# centerbody_Combine.net
KiCad netlist of a schematic drawn in EAGLE
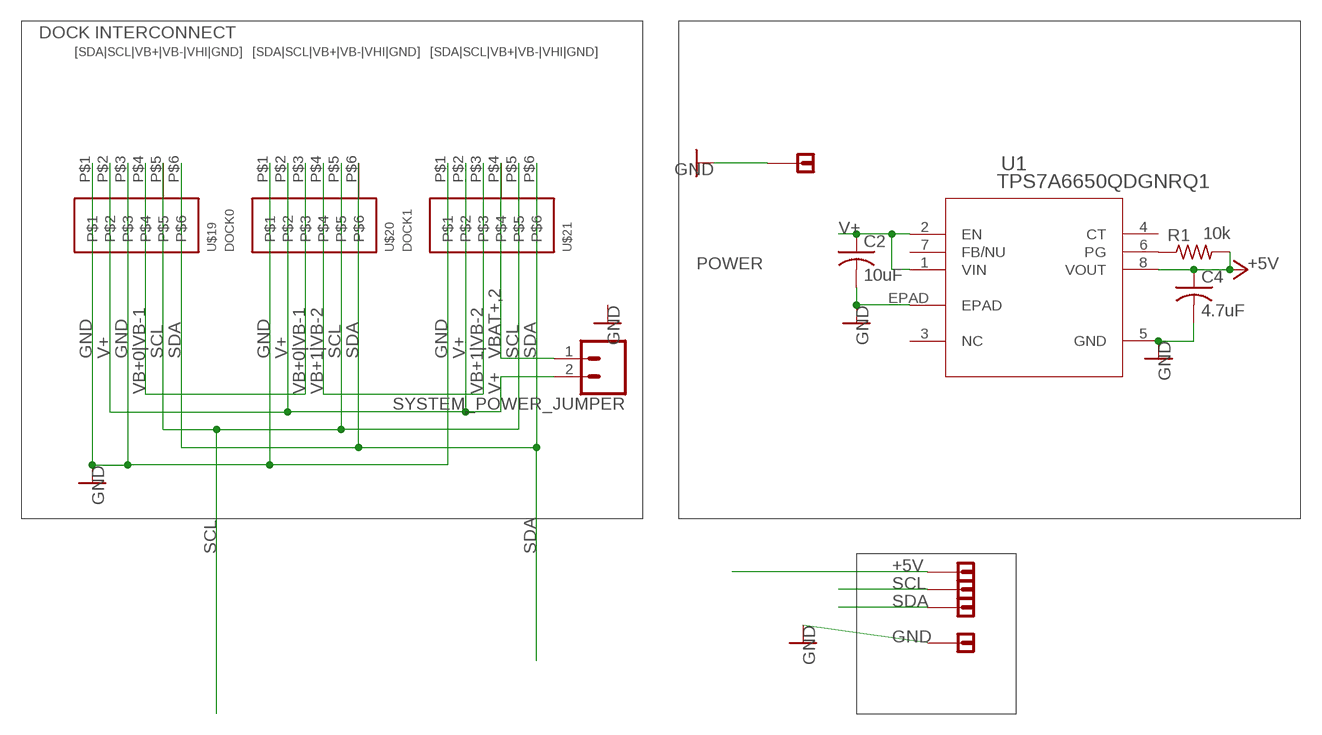
[diagram p0: schematic, sheet 1]

(export (version "E")
  (design (tool "Eeschema 10.0.6"))
  (components
    (comp (ref "C2")
      (value "10uF")
      (footprint "eagle-import:C1206")
      (libsource (lib "eagle-import") (part "C-USC1206"))
    )
    (comp (ref "C4")
      (value "4.7uF")
      (footprint "eagle-import:C0402")
      (libsource (lib "eagle-import") (part "resistor_348_C-USC0402"))
    )
    (comp (ref "R1")
      (value "10k")
      (footprint "eagle-import:R0402")
      (libsource (lib "eagle-import") (part "R-US_R0402"))
    )
    (comp (ref "SYSTEM_POWER_JUMPER")
      (value "CONN_02")
      (footprint "eagle-import:1X02")
      (libsource (lib "eagle-import") (part "CONN_02"))
    )
    (comp (ref "U$1")
      (value "SIMPLE_VIA_CONNECTION")
      (footprint "eagle-import:SIMPLEVIA")
      (libsource (lib "eagle-import") (part "SIMPLE_VIA_CONNECTION"))
    )
    (comp (ref "U$3")
      (value "SIMPLE_VIA_CONNECTION")
      (footprint "eagle-import:SIMPLEVIA")
      (libsource (lib "eagle-import") (part "SIMPLE_VIA_CONNECTION"))
    )
    (comp (ref "U$4")
      (value "SIMPLE_VIA_CONNECTION")
      (footprint "eagle-import:SIMPLEVIA")
      (libsource (lib "eagle-import") (part "SIMPLE_VIA_CONNECTION"))
    )
    (comp (ref "U$7")
      (value "SIMPLE_VIA_CONNECTION")
      (footprint "eagle-import:SIMPLEVIA")
      (libsource (lib "eagle-import") (part "SIMPLE_VIA_CONNECTION"))
    )
    (comp (ref "U$9")
      (value "SIMPLE_VIA_CONNECTION")
      (footprint "eagle-import:SIMPLEVIA")
      (libsource (lib "eagle-import") (part "SIMPLE_VIA_CONNECTION"))
    )
    (comp (ref "U$19")
      (value "DOCK0")
      (footprint "eagle-import:COMPACT_6CONN_STRAIGHT")
      (libsource (lib "eagle-import") (part "COMPACT_6CONNSTRAIGHT"))
    )
    (comp (ref "U$20")
      (value "DOCK1")
      (footprint "eagle-import:COMPACT_6CONN_STRAIGHT")
      (libsource (lib "eagle-import") (part "COMPACT_6CONNSTRAIGHT"))
    )
    (comp (ref "U$21")
      (value "DOCK_2")
      (footprint "eagle-import:COMPACT_6CONN_STRAIGHT")
      (libsource (lib "eagle-import") (part "COMPACT_6CONNSTRAIGHT"))
    )
    (comp (ref "U1")
      (value "TPS7A6650QDGNRQ1")
      (footprint "eagle-import:DGN8_1P57X1P89")
      (libsource (lib "eagle-import") (part "TPS7A6650QDGNRQ1"))
    )
  )
  (nets
    (net (code "1") (name "+5V") (class "Default")
      (node (ref "C4") (pin "1") (pinfunction "1_1") (pintype "passive"))
      (node (ref "R1") (pin "2") (pinfunction "2_2") (pintype "passive"))
      (node (ref "U$7") (pin "P$1") (pinfunction "1_P$1") (pintype "passive"))
      (node (ref "U1") (pin "8") (pinfunction "VOUT_8") (pintype "output"))
    )
    (net (code "2") (name "/SCL") (class "Default")
      (node (ref "U$19") (pin "P$5") (pinfunction "P$5_P$5") (pintype "bidirectional"))
      (node (ref "U$20") (pin "P$5") (pinfunction "P$5_P$5") (pintype "bidirectional"))
      (node (ref "U$21") (pin "P$5") (pinfunction "P$5_P$5") (pintype "bidirectional"))
      (node (ref "U$9") (pin "P$1") (pinfunction "1_P$1") (pintype "passive"))
    )
    (net (code "3") (name "/SDA") (class "Default")
      (node (ref "U$19") (pin "P$6") (pinfunction "P$6_P$6") (pintype "bidirectional"))
      (node (ref "U$20") (pin "P$6") (pinfunction "P$6_P$6") (pintype "bidirectional"))
      (node (ref "U$21") (pin "P$6") (pinfunction "P$6_P$6") (pintype "bidirectional"))
      (node (ref "U$4") (pin "P$1") (pinfunction "1_P$1") (pintype "passive"))
    )
    (net (code "4") (name "/V+") (class "Default")
      (node (ref "C2") (pin "1") (pinfunction "1_1") (pintype "passive"))
      (node (ref "SYSTEM_POWER_JUMPER") (pin "2") (pinfunction "2_2") (pintype "passive"))
      (node (ref "U$19") (pin "P$2") (pinfunction "P$2_P$2") (pintype "bidirectional"))
      (node (ref "U$20") (pin "P$2") (pinfunction "P$2_P$2") (pintype "bidirectional"))
      (node (ref "U$21") (pin "P$2") (pinfunction "P$2_P$2") (pintype "bidirectional"))
      (node (ref "U1") (pin "1") (pinfunction "VIN_1") (pintype "input"))
      (node (ref "U1") (pin "2") (pinfunction "EN_2") (pintype "input"))
    )
    (net (code "5") (name "/VB+0|VB-1") (class "Default")
      (node (ref "U$19") (pin "P$4") (pinfunction "P$4_P$4") (pintype "bidirectional"))
      (node (ref "U$20") (pin "P$3") (pinfunction "P$3_P$3") (pintype "bidirectional"))
    )
    (net (code "6") (name "/VB+1|VB-2") (class "Default")
      (node (ref "U$20") (pin "P$4") (pinfunction "P$4_P$4") (pintype "bidirectional"))
      (node (ref "U$21") (pin "P$3") (pinfunction "P$3_P$3") (pintype "bidirectional"))
    )
    (net (code "7") (name "/VBAT+,2") (class "Default")
      (node (ref "SYSTEM_POWER_JUMPER") (pin "1") (pinfunction "1_1") (pintype "passive"))
      (node (ref "U$21") (pin "P$4") (pinfunction "P$4_P$4") (pintype "bidirectional"))
    )
    (net (code "8") (name "GND") (class "Default")
      (node (ref "C2") (pin "2") (pinfunction "2_2") (pintype "passive"))
      (node (ref "C4") (pin "2") (pinfunction "2_2") (pintype "passive"))
      (node (ref "U$1") (pin "P$1") (pinfunction "1_P$1") (pintype "passive"))
      (node (ref "U$19") (pin "P$1") (pinfunction "P$1_P$1") (pintype "bidirectional"))
      (node (ref "U$19") (pin "P$3") (pinfunction "P$3_P$3") (pintype "bidirectional"))
      (node (ref "U$20") (pin "P$1") (pinfunction "P$1_P$1") (pintype "bidirectional"))
      (node (ref "U$21") (pin "P$1") (pinfunction "P$1_P$1") (pintype "bidirectional"))
      (node (ref "U$3") (pin "P$1") (pinfunction "1_P$1") (pintype "passive"))
      (node (ref "U1") (pin "5") (pinfunction "GND_5") (pintype "power_in"))
      (node (ref "U1") (pin "EPAD") (pinfunction "EPAD_EPAD") (pintype "passive"))
    )
    (net (code "9") (name "Net-(U1-PG)") (class "Default")
      (node (ref "R1") (pin "1") (pinfunction "1_1") (pintype "passive"))
      (node (ref "U1") (pin "6") (pinfunction "PG_6") (pintype "output"))
    )
    (net (code "10") (name "unconnected-(U1-CT-Pad4)") (class "Default")
      (node (ref "U1") (pin "4") (pinfunction "CT_4") (pintype "output"))
    )
    (net (code "11") (name "unconnected-(U1-FB{slash}NU-Pad7)") (class "Default")
      (node (ref "U1") (pin "7") (pinfunction "FB/NU_7") (pintype "input"))
    )
    (net (code "12") (name "unconnected-(U1-NC-Pad3)") (class "Default")
      (node (ref "U1") (pin "3") (pinfunction "NC_3") (pintype "no_connect"))
    )
  )
)
